# Robotan.net
KiCad netlist of a schematic drawn in EAGLE
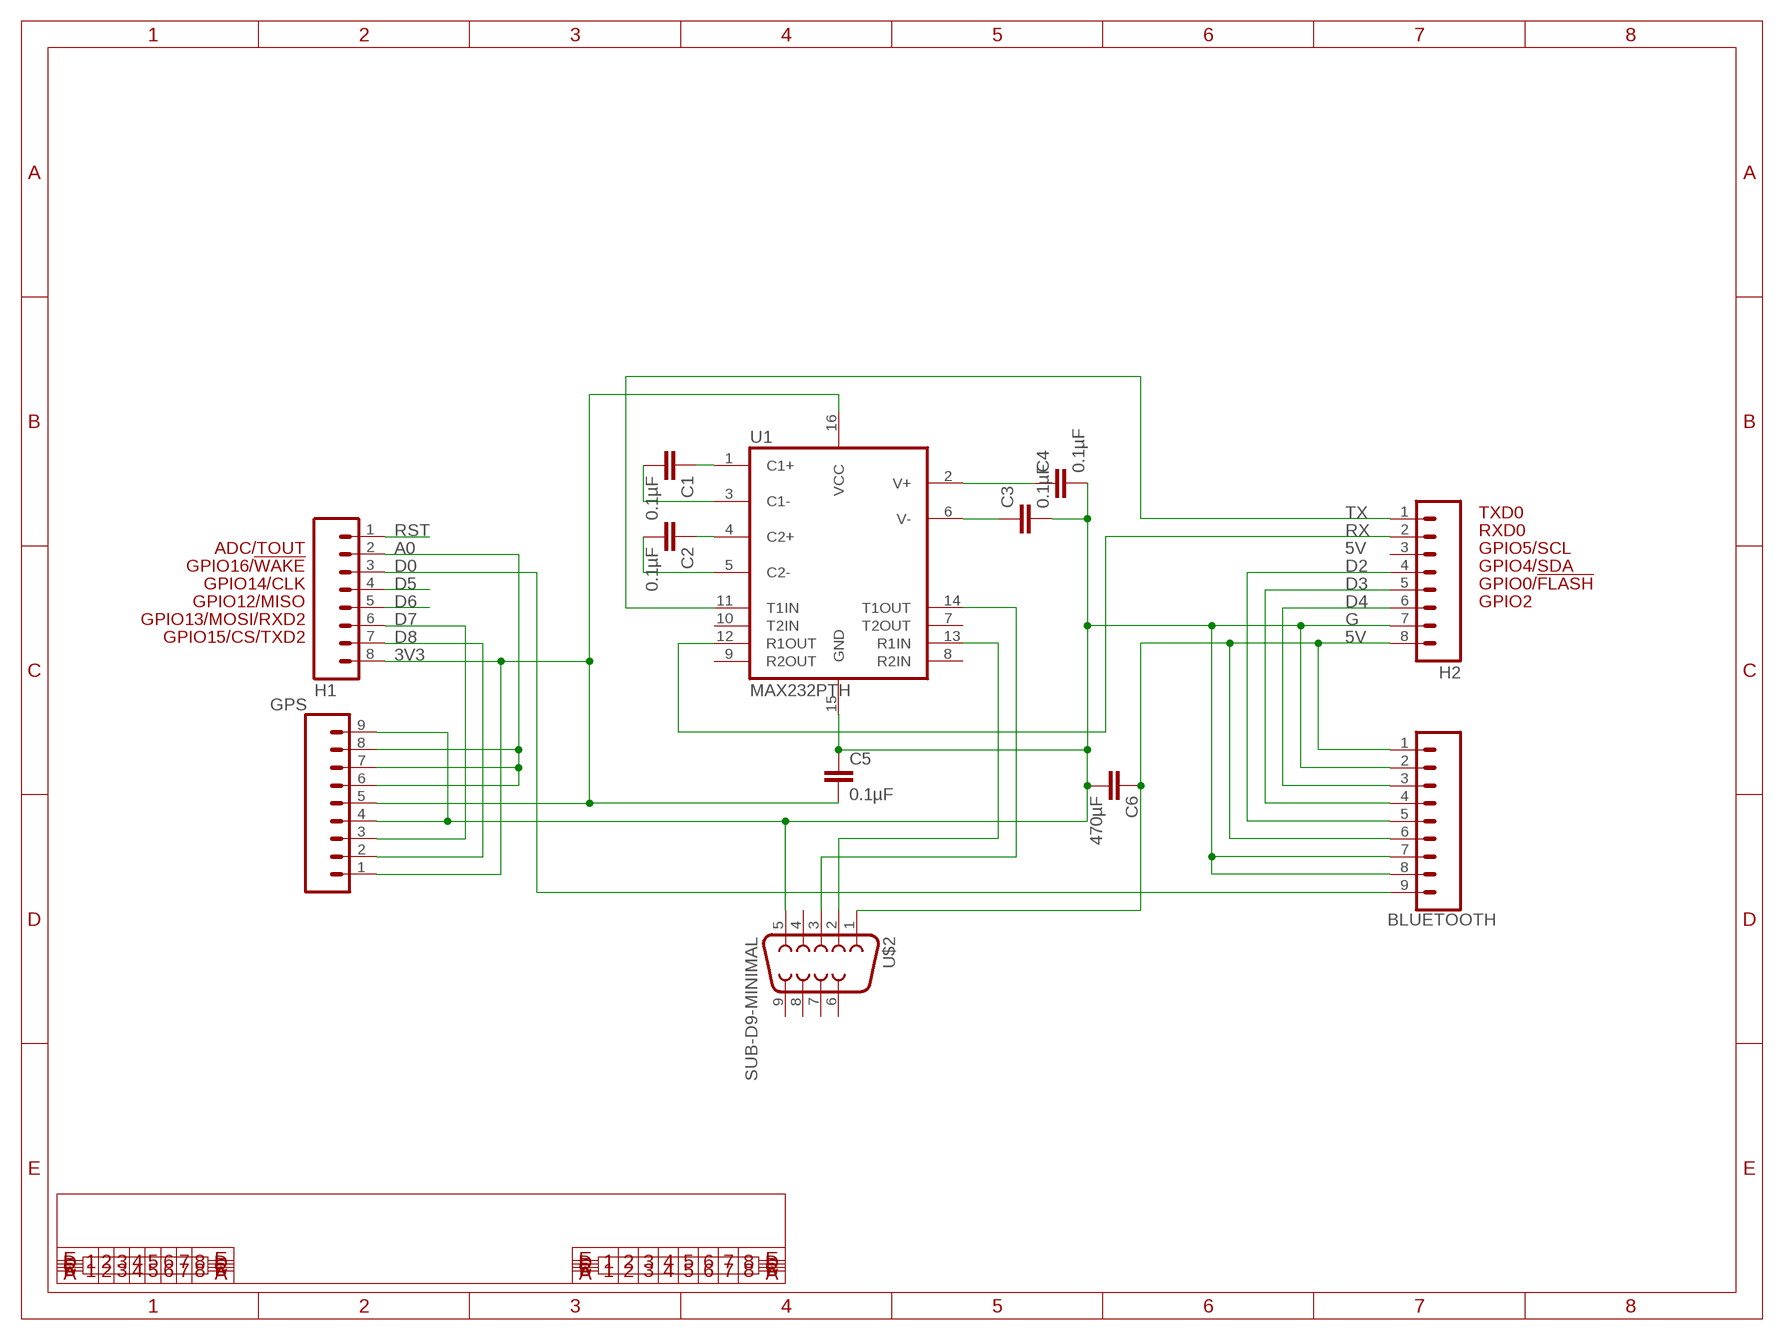
[diagram p0: schematic, sheet 1]

(export (version "E")
  (design (tool "Eeschema 10.0.6"))
  (components
    (comp (ref "BLUETOOTH")
      (value "M09")
      (footprint "eagle-import:1X09")
      (libsource (lib "eagle-import") (part "M09"))
    )
    (comp (ref "C1")
      (value "0.1µF")
      (footprint "eagle-import:CAP-PTH-SMALL-KIT")
      (libsource (lib "eagle-import") (part "0.1UF-50V-20%(PTH)KIT-EZ"))
    )
    (comp (ref "C2")
      (value "0.1µF")
      (footprint "eagle-import:CAP-PTH-SMALL-KIT")
      (libsource (lib "eagle-import") (part "0.1UF-50V-20%(PTH)KIT-EZ"))
    )
    (comp (ref "C3")
      (value "0.1µF")
      (footprint "eagle-import:CAP-PTH-SMALL-KIT")
      (libsource (lib "eagle-import") (part "0.1UF-50V-20%(PTH)KIT-EZ"))
    )
    (comp (ref "C4")
      (value "0.1µF")
      (footprint "eagle-import:CAP-PTH-SMALL-KIT")
      (libsource (lib "eagle-import") (part "0.1UF-50V-20%(PTH)KIT-EZ"))
    )
    (comp (ref "C5")
      (value "0.1µF")
      (footprint "eagle-import:CAP-PTH-SMALL-KIT")
      (libsource (lib "eagle-import") (part "0.1UF-50V-20%(PTH)KIT-EZ"))
    )
    (comp (ref "C6")
      (value "470µF")
      (footprint "eagle-import:CAP-PTH-SMALL-KIT")
      (libsource (lib "eagle-import") (part "0.1UF-50V-20%(PTH)KIT-EZ"))
    )
    (comp (ref "GPS")
      (value "M09")
      (footprint "eagle-import:1X09")
      (libsource (lib "eagle-import") (part "M09"))
    )
    (comp (ref "H1")
      (value "M08")
      (footprint "eagle-import:1X08")
      (libsource (lib "eagle-import") (part "M08"))
    )
    (comp (ref "H2")
      (value "M08")
      (footprint "eagle-import:1X08")
      (libsource (lib "eagle-import") (part "M08"))
    )
    (comp (ref "U$2")
      (value "SUB-D9-MINIMAL")
      (footprint "eagle-import:SUB-D9-MINIMAL")
      (libsource (lib "eagle-import") (part "SUB-D9-MINIMAL"))
    )
    (comp (ref "U1")
      (value "MAX232PTH")
      (footprint "eagle-import:DIL16")
      (libsource (lib "eagle-import") (part "MAX232PTH"))
    )
  )
  (nets
    (net (code "1") (name "/3V3") (class "Default")
      (node (ref "C5") (pin "2") (pinfunction "2_2") (pintype "passive"))
      (node (ref "GPS") (pin "1") (pinfunction "1_1") (pintype "passive"))
      (node (ref "GPS") (pin "5") (pinfunction "5_5") (pintype "passive"))
      (node (ref "H1") (pin "8") (pinfunction "8_8") (pintype "passive"))
      (node (ref "U1") (pin "16") (pinfunction "VCC_16") (pintype "bidirectional"))
    )
    (net (code "2") (name "/5V") (class "Default")
      (node (ref "BLUETOOTH") (pin "1") (pinfunction "1_1") (pintype "passive"))
      (node (ref "BLUETOOTH") (pin "6") (pinfunction "6_6") (pintype "passive"))
      (node (ref "C6") (pin "1") (pinfunction "1_1") (pintype "passive"))
      (node (ref "H2") (pin "8") (pinfunction "8_8") (pintype "passive"))
      (node (ref "U$2") (pin "1") (pinfunction "1_1") (pintype "passive"))
    )
    (net (code "3") (name "/A0") (class "Default")
      (node (ref "GPS") (pin "6") (pinfunction "6_6") (pintype "passive"))
      (node (ref "GPS") (pin "7") (pinfunction "7_7") (pintype "passive"))
      (node (ref "GPS") (pin "8") (pinfunction "8_8") (pintype "passive"))
      (node (ref "H1") (pin "2") (pinfunction "2_2") (pintype "passive"))
    )
    (net (code "4") (name "/D0") (class "Default")
      (node (ref "BLUETOOTH") (pin "9") (pinfunction "9_9") (pintype "passive"))
      (node (ref "H1") (pin "3") (pinfunction "3_3") (pintype "passive"))
    )
    (net (code "5") (name "/D2") (class "Default")
      (node (ref "BLUETOOTH") (pin "5") (pinfunction "5_5") (pintype "passive"))
      (node (ref "H2") (pin "4") (pinfunction "4_4") (pintype "passive"))
    )
    (net (code "6") (name "/D3") (class "Default")
      (node (ref "BLUETOOTH") (pin "4") (pinfunction "4_4") (pintype "passive"))
      (node (ref "H2") (pin "5") (pinfunction "5_5") (pintype "passive"))
    )
    (net (code "7") (name "/D4") (class "Default")
      (node (ref "BLUETOOTH") (pin "3") (pinfunction "3_3") (pintype "passive"))
      (node (ref "H2") (pin "6") (pinfunction "6_6") (pintype "passive"))
    )
    (net (code "8") (name "/D5") (class "Default")
      (node (ref "H1") (pin "4") (pinfunction "4_4") (pintype "passive"))
    )
    (net (code "9") (name "/D6") (class "Default")
      (node (ref "H1") (pin "5") (pinfunction "5_5") (pintype "passive"))
    )
    (net (code "10") (name "/D7") (class "Default")
      (node (ref "GPS") (pin "3") (pinfunction "3_3") (pintype "passive"))
      (node (ref "H1") (pin "6") (pinfunction "6_6") (pintype "passive"))
    )
    (net (code "11") (name "/D8") (class "Default")
      (node (ref "GPS") (pin "2") (pinfunction "2_2") (pintype "passive"))
      (node (ref "H1") (pin "7") (pinfunction "7_7") (pintype "passive"))
    )
    (net (code "12") (name "/G") (class "Default")
      (node (ref "BLUETOOTH") (pin "2") (pinfunction "2_2") (pintype "passive"))
      (node (ref "BLUETOOTH") (pin "7") (pinfunction "7_7") (pintype "passive"))
      (node (ref "BLUETOOTH") (pin "8") (pinfunction "8_8") (pintype "passive"))
      (node (ref "C3") (pin "2") (pinfunction "2_2") (pintype "passive"))
      (node (ref "C4") (pin "2") (pinfunction "2_2") (pintype "passive"))
      (node (ref "C5") (pin "1") (pinfunction "1_1") (pintype "passive"))
      (node (ref "C6") (pin "2") (pinfunction "2_2") (pintype "passive"))
      (node (ref "GPS") (pin "4") (pinfunction "4_4") (pintype "passive"))
      (node (ref "GPS") (pin "9") (pinfunction "9_9") (pintype "passive"))
      (node (ref "H2") (pin "7") (pinfunction "7_7") (pintype "passive"))
      (node (ref "U$2") (pin "5") (pinfunction "5_5") (pintype "passive"))
      (node (ref "U1") (pin "15") (pinfunction "GND_15") (pintype "bidirectional"))
    )
    (net (code "13") (name "/RST") (class "Default")
      (node (ref "H1") (pin "1") (pinfunction "1_1") (pintype "passive"))
    )
    (net (code "14") (name "/RX") (class "Default")
      (node (ref "H2") (pin "2") (pinfunction "2_2") (pintype "passive"))
      (node (ref "U1") (pin "12") (pinfunction "R1OUT_12") (pintype "output"))
    )
    (net (code "15") (name "/TX") (class "Default")
      (node (ref "H2") (pin "1") (pinfunction "1_1") (pintype "passive"))
      (node (ref "U1") (pin "11") (pinfunction "T1IN_11") (pintype "input"))
    )
    (net (code "16") (name "Net-(U1-C1+)") (class "Default")
      (node (ref "C1") (pin "1") (pinfunction "1_1") (pintype "passive"))
      (node (ref "U1") (pin "1") (pinfunction "C1+_1") (pintype "bidirectional"))
    )
    (net (code "17") (name "Net-(U1-C1-)") (class "Default")
      (node (ref "C1") (pin "2") (pinfunction "2_2") (pintype "passive"))
      (node (ref "U1") (pin "3") (pinfunction "C1-_3") (pintype "bidirectional"))
    )
    (net (code "18") (name "Net-(U1-C2+)") (class "Default")
      (node (ref "C2") (pin "1") (pinfunction "1_1") (pintype "passive"))
      (node (ref "U1") (pin "4") (pinfunction "C2+_4") (pintype "bidirectional"))
    )
    (net (code "19") (name "Net-(U1-C2-)") (class "Default")
      (node (ref "C2") (pin "2") (pinfunction "2_2") (pintype "passive"))
      (node (ref "U1") (pin "5") (pinfunction "C2-_5") (pintype "bidirectional"))
    )
    (net (code "20") (name "Net-(U1-R1IN)") (class "Default")
      (node (ref "U$2") (pin "2") (pinfunction "2_2") (pintype "passive"))
      (node (ref "U1") (pin "13") (pinfunction "R1IN_13") (pintype "input"))
    )
    (net (code "21") (name "Net-(U1-T1OUT)") (class "Default")
      (node (ref "U$2") (pin "3") (pinfunction "3_3") (pintype "passive"))
      (node (ref "U1") (pin "14") (pinfunction "T1OUT_14") (pintype "output"))
    )
    (net (code "22") (name "Net-(U1-V+)") (class "Default")
      (node (ref "C4") (pin "1") (pinfunction "1_1") (pintype "passive"))
      (node (ref "U1") (pin "2") (pinfunction "V+_2") (pintype "bidirectional"))
    )
    (net (code "23") (name "Net-(U1-V-)") (class "Default")
      (node (ref "C3") (pin "1") (pinfunction "1_1") (pintype "passive"))
      (node (ref "U1") (pin "6") (pinfunction "V-_6") (pintype "bidirectional"))
    )
    (net (code "24") (name "unconnected-(H2-Pad3)") (class "Default")
      (node (ref "H2") (pin "3") (pinfunction "3_3") (pintype "passive"))
    )
    (net (code "25") (name "unconnected-(U$2-Pad4)") (class "Default")
      (node (ref "U$2") (pin "4") (pinfunction "4_4") (pintype "passive"))
    )
    (net (code "26") (name "unconnected-(U$2-Pad6)") (class "Default")
      (node (ref "U$2") (pin "6") (pinfunction "6_6") (pintype "passive"))
    )
    (net (code "27") (name "unconnected-(U$2-Pad7)") (class "Default")
      (node (ref "U$2") (pin "7") (pinfunction "7_7") (pintype "passive"))
    )
    (net (code "28") (name "unconnected-(U$2-Pad8)") (class "Default")
      (node (ref "U$2") (pin "8") (pinfunction "8_8") (pintype "passive"))
    )
    (net (code "29") (name "unconnected-(U$2-Pad9)") (class "Default")
      (node (ref "U$2") (pin "9") (pinfunction "9_9") (pintype "passive"))
    )
    (net (code "30") (name "unconnected-(U1-R2IN-Pad8)") (class "Default")
      (node (ref "U1") (pin "8") (pinfunction "R2IN_8") (pintype "input"))
    )
    (net (code "31") (name "unconnected-(U1-R2OUT-Pad9)") (class "Default")
      (node (ref "U1") (pin "9") (pinfunction "R2OUT_9") (pintype "output"))
    )
    (net (code "32") (name "unconnected-(U1-T2IN-Pad10)") (class "Default")
      (node (ref "U1") (pin "10") (pinfunction "T2IN_10") (pintype "input"))
    )
    (net (code "33") (name "unconnected-(U1-T2OUT-Pad7)") (class "Default")
      (node (ref "U1") (pin "7") (pinfunction "T2OUT_7") (pintype "output"))
    )
  )
)
